# HBridge.net
KiCad netlist of a schematic drawn in Altium Designer
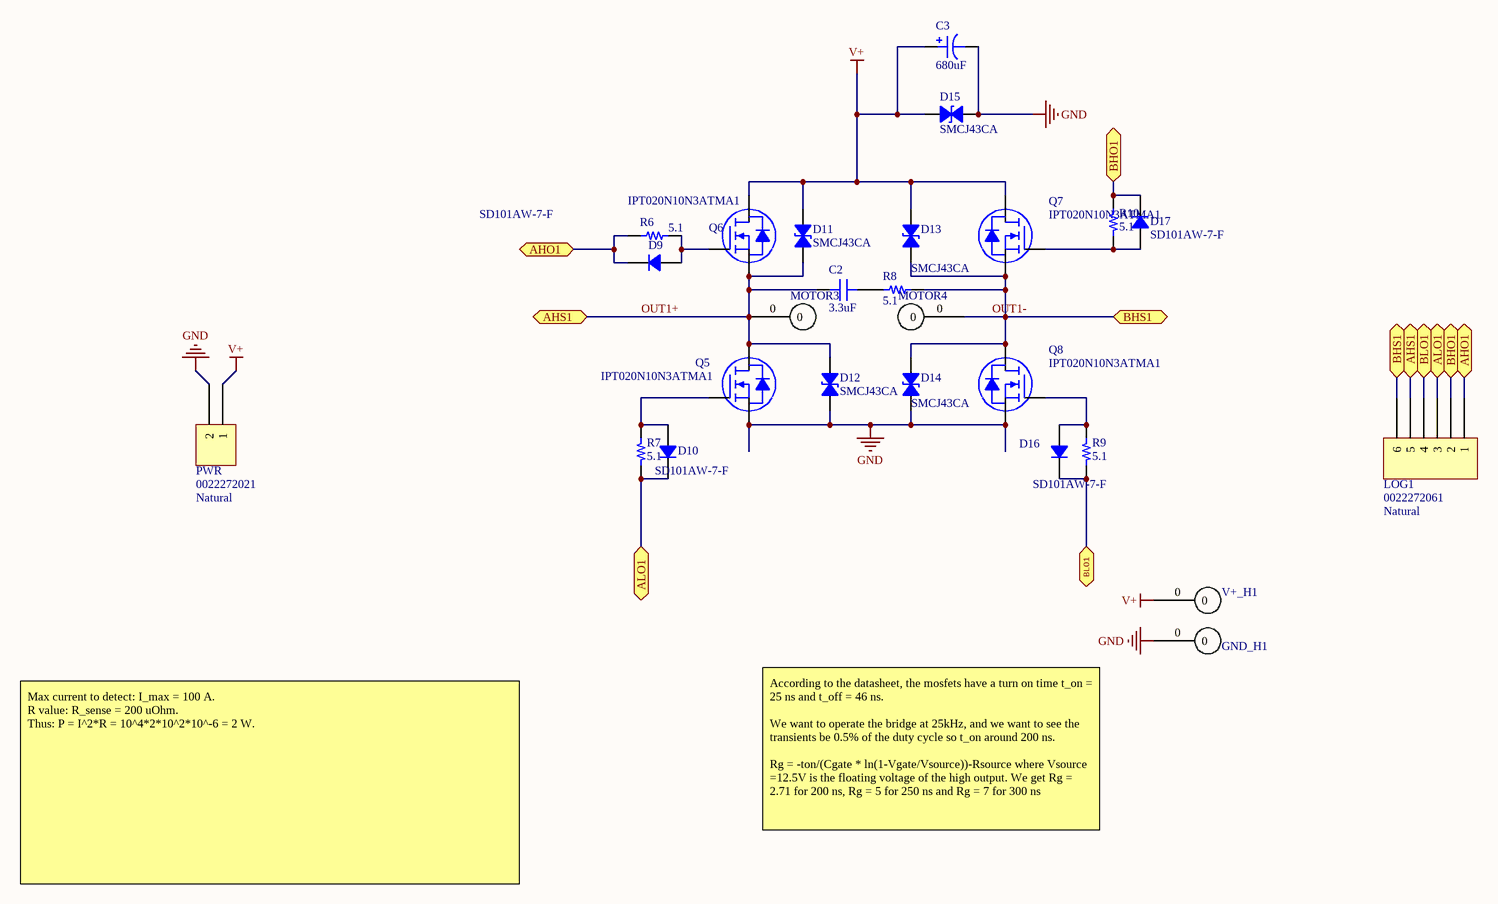
[diagram p0: HBridge.SchDoc]

(export (version "E")
  (design (tool "Eeschema 10.0.6"))
  (components
    (comp (ref "C2")
      (value "3.3uF")
      (footprint "CAP 1206/3216 - 1.8MM")
      (description "CAP CER 3.3UF 100V X7S 1206")
      (fields
        (field (name "PART NUMBER") "CGA5L3X7S2A335K160AB")
        (field (name "MANUFACTURER") "TDK Corporation")
      )
      (libsource (lib "Celestial Library Database") (part "Capacitor"))
    )
    (comp (ref "C3")
      (value "680uF")
      (footprint "Radial Capacitor 12.5mm")
      (description "CAP ALUM 680UF 20% 63V Through Hole")
      (fields (field (name "PART NUMBER") "EEUFR1J681L") (field (name "MANUFACTURER") "Panasonic"))
      (libsource (lib "Celestial Library Database") (part "Polarised Capacitor"))
    )
    (comp (ref "D9")
      (value "SD101AW-7-F")
      (footprint "SOD-123")
      (description "DIODE SCHOTTKY 60V 15MA SOD123")
      (fields (field (name "MANUFACTURER") "Diodes Incorporated"))
      (libsource (lib "Celestial Library Database") (part "Diode"))
    )
    (comp (ref "D10")
      (value "SD101AW-7-F")
      (footprint "SOD-123")
      (description "DIODE SCHOTTKY 60V 15MA SOD123")
      (fields (field (name "MANUFACTURER") "Diodes Incorporated"))
      (libsource (lib "Celestial Library Database") (part "Diode"))
    )
    (comp (ref "D11")
      (value "SMCJ43CA")
      (footprint "ST DO214AB SMC")
      (description "TVS DIODE 43VWM 69.4VC SMC")
      (fields (field (name "MANUFACTURER") "FAIRCHILD"))
      (libsource (lib "Celestial Library Database") (part "Diode Zener Bidirectional"))
    )
    (comp (ref "D12")
      (value "SMCJ43CA")
      (footprint "ST DO214AB SMC")
      (description "TVS DIODE 43VWM 69.4VC SMC")
      (fields (field (name "MANUFACTURER") "FAIRCHILD"))
      (libsource (lib "Celestial Library Database") (part "Diode Zener Bidirectional"))
    )
    (comp (ref "D13")
      (value "SMCJ43CA")
      (footprint "ST DO214AB SMC")
      (description "TVS DIODE 43VWM 69.4VC SMC")
      (fields (field (name "MANUFACTURER") "FAIRCHILD"))
      (libsource (lib "Celestial Library Database") (part "Diode Zener Bidirectional"))
    )
    (comp (ref "D14")
      (value "SMCJ43CA")
      (footprint "ST DO214AB SMC")
      (description "TVS DIODE 43VWM 69.4VC SMC")
      (fields (field (name "MANUFACTURER") "FAIRCHILD"))
      (libsource (lib "Celestial Library Database") (part "Diode Zener Bidirectional"))
    )
    (comp (ref "D15")
      (value "SMCJ43CA")
      (footprint "ST DO214AB SMC")
      (description "TVS DIODE 43VWM 69.4VC SMC")
      (fields (field (name "MANUFACTURER") "FAIRCHILD"))
      (libsource (lib "Celestial Library Database") (part "Diode Zener Bidirectional"))
    )
    (comp (ref "D16")
      (value "SD101AW-7-F")
      (footprint "SOD-123")
      (description "DIODE SCHOTTKY 60V 15MA SOD123")
      (fields (field (name "MANUFACTURER") "Diodes Incorporated"))
      (libsource (lib "Celestial Library Database") (part "Diode"))
    )
    (comp (ref "D17")
      (value "SD101AW-7-F")
      (footprint "SOD-123")
      (description "DIODE SCHOTTKY 60V 15MA SOD123")
      (fields (field (name "MANUFACTURER") "Diodes Incorporated"))
      (libsource (lib "Celestial Library Database") (part "Diode"))
    )
    (comp (ref "GND_H1")
      (value "Cable Hole 6.54mm")
      (footprint "Cable Hole 6.54mm")
      (fields (field (name "PART NUMBER") "Cable Pad AWG 2"))
      (libsource (lib "Celestial Library Database") (part "Cable Hole 6.54mm"))
    )
    (comp (ref "LOG1")
      (value "0022272061")
      (footprint "MOLEX KK 0022272061")
      (description "CONN HEADER 6POS .100 VERT TIN")
      (fields (field (name "COLOUR") "Natural") (field (name "MANUFACTURER") "Molex, LLC"))
      (libsource (lib "Celestial Library Database") (part "6 Pin"))
    )
    (comp (ref "MOTOR3")
      (value "H1")
      (footprint "Cable Hole 6.54mm")
      (fields (field (name "PART NUMBER") "Cable Pad AWG 2"))
      (libsource (lib "Celestial Library Database") (part "Cable Hole 6.54mm"))
    )
    (comp (ref "MOTOR4")
      (value "H2")
      (footprint "Cable Hole 6.54mm")
      (fields (field (name "PART NUMBER") "Cable Pad AWG 2"))
      (libsource (lib "Celestial Library Database") (part "Cable Hole 6.54mm"))
    )
    (comp (ref "PWR")
      (value "0022272021")
      (footprint "MOLEX KK 0022272021")
      (description "CONN HEADER 2POS .100 VERT TIN")
      (fields (field (name "COLOUR") "Natural") (field (name "MANUFACTURER") "Molex, LLC"))
      (libsource (lib "Celestial Library Database") (part "2 Pin"))
    )
    (comp (ref "Q5")
      (value "IPT020N10N3ATMA1")
      (footprint "INFINEON PG-HSOF-8-1")
      (description "MOSFET N-CH 100V 300A 8HSOF")
      (fields (field (name "MANUFACTURER") "Infineon Technologies"))
      (libsource (lib "") (part "INFINEON MOSFET N-CH HSOF_1"))
    )
    (comp (ref "Q6")
      (value "IPT020N10N3ATMA1")
      (footprint "INFINEON PG-HSOF-8-1")
      (description "MOSFET N-CH 100V 300A 8HSOF")
      (fields (field (name "MANUFACTURER") "Infineon Technologies"))
      (libsource (lib "") (part "INFINEON MOSFET N-CH HSOF_1"))
    )
    (comp (ref "Q7")
      (value "IPT020N10N3ATMA1")
      (footprint "INFINEON PG-HSOF-8-1")
      (description "MOSFET N-CH 100V 300A 8HSOF")
      (fields (field (name "MANUFACTURER") "Infineon Technologies"))
      (libsource (lib "Celestial Library Database") (part "INFINEON MOSFET N-CH HSOF"))
    )
    (comp (ref "Q8")
      (value "IPT020N10N3ATMA1")
      (footprint "INFINEON PG-HSOF-8-1")
      (description "MOSFET N-CH 100V 300A 8HSOF")
      (fields (field (name "MANUFACTURER") "Infineon Technologies"))
      (libsource (lib "Celestial Library Database") (part "INFINEON MOSFET N-CH HSOF"))
    )
    (comp (ref "R6")
      (value "5.1")
      (footprint "RES 1206/3216")
      (description "RES SMD 5.1 OHM 5% 1/4W 1206")
      (fields
        (field (name "PART NUMBER") "ERJ-8GEYJ5R1V")
        (field (name "MANUFACTURER") "Panasonic Electronic Components")
      )
      (libsource (lib "Celestial Library Database") (part "Resistor"))
    )
    (comp (ref "R7")
      (value "5.1")
      (footprint "RES 1206/3216")
      (description "RES SMD 5.1 OHM 5% 1/4W 1206")
      (fields
        (field (name "PART NUMBER") "ERJ-8GEYJ5R1V")
        (field (name "MANUFACTURER") "Panasonic Electronic Components")
      )
      (libsource (lib "Celestial Library Database") (part "Resistor"))
    )
    (comp (ref "R8")
      (value "5.1")
      (footprint "RES 1206/3216")
      (description "RES SMD 5.1 OHM 5% 1/4W 1206")
      (fields
        (field (name "PART NUMBER") "ERJ-8GEYJ5R1V")
        (field (name "MANUFACTURER") "Panasonic Electronic Components")
      )
      (libsource (lib "Celestial Library Database") (part "Resistor"))
    )
    (comp (ref "R9")
      (value "5.1")
      (footprint "RES 1206/3216")
      (description "RES SMD 5.1 OHM 5% 1/4W 1206")
      (fields
        (field (name "PART NUMBER") "ERJ-8GEYJ5R1V")
        (field (name "MANUFACTURER") "Panasonic Electronic Components")
      )
      (libsource (lib "Celestial Library Database") (part "Resistor"))
    )
    (comp (ref "R10")
      (value "5.1")
      (footprint "RES 1206/3216")
      (description "RES SMD 5.1 OHM 5% 1/4W 1206")
      (fields
        (field (name "PART NUMBER") "ERJ-8GEYJ5R1V")
        (field (name "MANUFACTURER") "Panasonic Electronic Components")
      )
      (libsource (lib "Celestial Library Database") (part "Resistor"))
    )
    (comp (ref "V+_H1")
      (value "Cable Hole 6.54mm")
      (footprint "Cable Hole 6.54mm")
      (fields (field (name "PART NUMBER") "Cable Pad AWG 2"))
      (libsource (lib "Celestial Library Database") (part "Cable Hole 6.54mm"))
    )
  )
  (nets
    (net (code "1") (name "/AHO1") (class "Default")
      (node (ref "D9") (pin "2") (pinfunction "2_2") (pintype "passive"))
      (node (ref "LOG1") (pin "1") (pinfunction "1_1") (pintype "passive"))
      (node (ref "R6") (pin "1") (pinfunction "1_1") (pintype "passive"))
    )
    (net (code "2") (name "/ALO1") (class "Default")
      (node (ref "D10") (pin "2") (pinfunction "2_2") (pintype "passive"))
      (node (ref "LOG1") (pin "3") (pinfunction "3_3") (pintype "passive"))
      (node (ref "R7") (pin "2") (pinfunction "2_2") (pintype "passive"))
    )
    (net (code "3") (name "/BHO1") (class "Default")
      (node (ref "D17") (pin "2") (pinfunction "2_2") (pintype "passive"))
      (node (ref "LOG1") (pin "2") (pinfunction "2_2") (pintype "passive"))
      (node (ref "R10") (pin "1") (pinfunction "1_1") (pintype "passive"))
    )
    (net (code "4") (name "/BLO1") (class "Default")
      (node (ref "D16") (pin "2") (pinfunction "2_2") (pintype "passive"))
      (node (ref "LOG1") (pin "4") (pinfunction "4_4") (pintype "passive"))
      (node (ref "R9") (pin "2") (pinfunction "2_2") (pintype "passive"))
    )
    (net (code "5") (name "/OUT1+") (class "Default")
      (node (ref "C2") (pin "1") (pinfunction "1_1") (pintype "passive"))
      (node (ref "D11") (pin "1") (pinfunction "1_1") (pintype "passive"))
      (node (ref "D12") (pin "2") (pinfunction "2_2") (pintype "passive"))
      (node (ref "LOG1") (pin "5") (pinfunction "5_5") (pintype "passive"))
      (node (ref "MOTOR3") (pin "0") (pinfunction "0_0") (pintype "passive"))
      (node (ref "Q5") (pin "9") (pinfunction "D_9") (pintype "passive"))
      (node (ref "Q6") (pin "2") (pinfunction "S_2") (pintype "passive"))
      (node (ref "Q6") (pin "3") (pinfunction "S_3") (pintype "passive"))
      (node (ref "Q6") (pin "4") (pinfunction "S_4") (pintype "passive"))
      (node (ref "Q6") (pin "5") (pinfunction "S_5") (pintype "passive"))
      (node (ref "Q6") (pin "6") (pinfunction "S_6") (pintype "passive"))
      (node (ref "Q6") (pin "7") (pinfunction "S_7") (pintype "passive"))
      (node (ref "Q6") (pin "8") (pinfunction "S_8") (pintype "passive"))
    )
    (net (code "6") (name "/OUT1-") (class "Default")
      (node (ref "D13") (pin "1") (pinfunction "1_1") (pintype "passive"))
      (node (ref "D14") (pin "2") (pinfunction "2_2") (pintype "passive"))
      (node (ref "LOG1") (pin "6") (pinfunction "6_6") (pintype "passive"))
      (node (ref "MOTOR4") (pin "0") (pinfunction "0_0") (pintype "passive"))
      (node (ref "Q7") (pin "2") (pinfunction "S_2") (pintype "passive"))
      (node (ref "Q7") (pin "3") (pinfunction "S_3") (pintype "passive"))
      (node (ref "Q7") (pin "4") (pinfunction "S_4") (pintype "passive"))
      (node (ref "Q7") (pin "5") (pinfunction "S_5") (pintype "passive"))
      (node (ref "Q7") (pin "6") (pinfunction "S_6") (pintype "passive"))
      (node (ref "Q7") (pin "7") (pinfunction "S_7") (pintype "passive"))
      (node (ref "Q7") (pin "8") (pinfunction "S_8") (pintype "passive"))
      (node (ref "Q8") (pin "9") (pinfunction "D_9") (pintype "passive"))
      (node (ref "R8") (pin "2") (pinfunction "2_2") (pintype "passive"))
    )
    (net (code "7") (name "GND") (class "Default")
      (node (ref "C3") (pin "2") (pinfunction "2_2") (pintype "passive"))
      (node (ref "D12") (pin "1") (pinfunction "1_1") (pintype "passive"))
      (node (ref "D14") (pin "1") (pinfunction "1_1") (pintype "passive"))
      (node (ref "D15") (pin "2") (pinfunction "2_2") (pintype "passive"))
      (node (ref "GND_H1") (pin "0") (pinfunction "0_0") (pintype "passive"))
      (node (ref "PWR") (pin "2") (pinfunction "2_2") (pintype "passive"))
      (node (ref "Q5") (pin "2") (pinfunction "S_2") (pintype "passive"))
      (node (ref "Q5") (pin "3") (pinfunction "S_3") (pintype "passive"))
      (node (ref "Q5") (pin "4") (pinfunction "S_4") (pintype "passive"))
      (node (ref "Q5") (pin "5") (pinfunction "S_5") (pintype "passive"))
      (node (ref "Q5") (pin "6") (pinfunction "S_6") (pintype "passive"))
      (node (ref "Q5") (pin "7") (pinfunction "S_7") (pintype "passive"))
      (node (ref "Q5") (pin "8") (pinfunction "S_8") (pintype "passive"))
      (node (ref "Q8") (pin "2") (pinfunction "S_2") (pintype "passive"))
      (node (ref "Q8") (pin "3") (pinfunction "S_3") (pintype "passive"))
      (node (ref "Q8") (pin "4") (pinfunction "S_4") (pintype "passive"))
      (node (ref "Q8") (pin "5") (pinfunction "S_5") (pintype "passive"))
      (node (ref "Q8") (pin "6") (pinfunction "S_6") (pintype "passive"))
      (node (ref "Q8") (pin "7") (pinfunction "S_7") (pintype "passive"))
      (node (ref "Q8") (pin "8") (pinfunction "S_8") (pintype "passive"))
    )
    (net (code "8") (name "Net-(C2-Pad2)") (class "Default")
      (node (ref "C2") (pin "2") (pinfunction "2_2") (pintype "passive"))
      (node (ref "R8") (pin "1") (pinfunction "1_1") (pintype "passive"))
    )
    (net (code "9") (name "Net-(Q5-G)") (class "Default")
      (node (ref "D10") (pin "1") (pinfunction "1_1") (pintype "passive"))
      (node (ref "Q5") (pin "1") (pinfunction "G_1") (pintype "passive"))
      (node (ref "R7") (pin "1") (pinfunction "1_1") (pintype "passive"))
    )
    (net (code "10") (name "Net-(Q6-G)") (class "Default")
      (node (ref "D9") (pin "1") (pinfunction "1_1") (pintype "passive"))
      (node (ref "Q6") (pin "1") (pinfunction "G_1") (pintype "passive"))
      (node (ref "R6") (pin "2") (pinfunction "2_2") (pintype "passive"))
    )
    (net (code "11") (name "Net-(Q7-G)") (class "Default")
      (node (ref "D17") (pin "1") (pinfunction "1_1") (pintype "passive"))
      (node (ref "Q7") (pin "1") (pinfunction "G_1") (pintype "passive"))
      (node (ref "R10") (pin "2") (pinfunction "2_2") (pintype "passive"))
    )
    (net (code "12") (name "Net-(Q8-G)") (class "Default")
      (node (ref "D16") (pin "1") (pinfunction "1_1") (pintype "passive"))
      (node (ref "Q8") (pin "1") (pinfunction "G_1") (pintype "passive"))
      (node (ref "R9") (pin "1") (pinfunction "1_1") (pintype "passive"))
    )
    (net (code "13") (name "V+") (class "Default")
      (node (ref "C3") (pin "1") (pinfunction "1_1") (pintype "passive"))
      (node (ref "D11") (pin "2") (pinfunction "2_2") (pintype "passive"))
      (node (ref "D13") (pin "2") (pinfunction "2_2") (pintype "passive"))
      (node (ref "D15") (pin "1") (pinfunction "1_1") (pintype "passive"))
      (node (ref "PWR") (pin "1") (pinfunction "1_1") (pintype "passive"))
      (node (ref "Q6") (pin "9") (pinfunction "D_9") (pintype "passive"))
      (node (ref "Q7") (pin "9") (pinfunction "D_9") (pintype "passive"))
      (node (ref "V+_H1") (pin "0") (pinfunction "0_0") (pintype "passive"))
    )
  )
)
